# msp430_f249_ctk.net
KiCad netlist of a schematic drawn in EAGLE
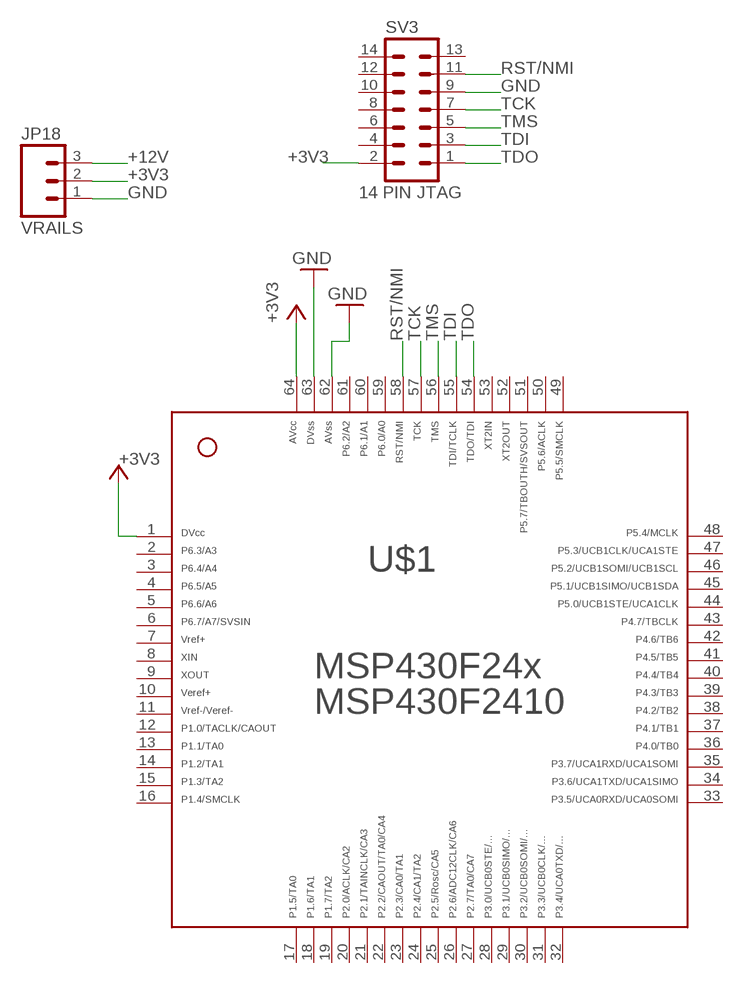
[diagram p0: schematic, sheet 1]

(export (version "E")
  (design (tool "Eeschema 10.0.6"))
  (components
    (comp (ref "JP18")
      (value "VRAILS")
      (footprint "eagle-import:SCREWTERMINAL-3.5MM-3")
      (libsource (lib "eagle-import") (part "M03SCREW"))
    )
    (comp (ref "SV3")
      (value "14 PIN JTAG")
      (footprint "eagle-import:ML14")
      (libsource (lib "eagle-import") (part "ML14"))
    )
    (comp (ref "U$1")
      (value "F24[X/10]---PM64")
      (footprint "eagle-import:PM_PAG64")
      (libsource (lib "eagle-import") (part "F24[X/10]---PM64"))
    )
  )
  (nets
    (net (code "1") (name "+3V3") (class "Default")
      (node (ref "JP18") (pin "2") (pinfunction "2_2") (pintype "passive"))
      (node (ref "SV3") (pin "2") (pinfunction "2_2") (pintype "passive"))
      (node (ref "U$1") (pin "1") (pinfunction "1_1") (pintype "power_in"))
      (node (ref "U$1") (pin "64") (pinfunction "64_64") (pintype "power_in"))
    )
    (net (code "2") (name "/+12V") (class "Default")
      (node (ref "JP18") (pin "3") (pinfunction "3_3") (pintype "passive"))
    )
    (net (code "3") (name "/RST{slash}NMI") (class "Default")
      (node (ref "SV3") (pin "11") (pinfunction "11_11") (pintype "passive"))
      (node (ref "U$1") (pin "58") (pinfunction "58_58") (pintype "input"))
    )
    (net (code "4") (name "/TCK") (class "Default")
      (node (ref "SV3") (pin "7") (pinfunction "7_7") (pintype "passive"))
      (node (ref "U$1") (pin "57") (pinfunction "57_57") (pintype "input"))
    )
    (net (code "5") (name "/TDI") (class "Default")
      (node (ref "SV3") (pin "3") (pinfunction "3_3") (pintype "passive"))
      (node (ref "U$1") (pin "55") (pinfunction "55_55") (pintype "input"))
    )
    (net (code "6") (name "/TDO") (class "Default")
      (node (ref "SV3") (pin "1") (pinfunction "1_1") (pintype "passive"))
      (node (ref "U$1") (pin "54") (pinfunction "54_54") (pintype "bidirectional"))
    )
    (net (code "7") (name "/TMS") (class "Default")
      (node (ref "SV3") (pin "5") (pinfunction "5_5") (pintype "passive"))
      (node (ref "U$1") (pin "56") (pinfunction "56_56") (pintype "input"))
    )
    (net (code "8") (name "GND") (class "Default")
      (node (ref "JP18") (pin "1") (pinfunction "1_1") (pintype "passive"))
      (node (ref "SV3") (pin "9") (pinfunction "9_9") (pintype "passive"))
      (node (ref "U$1") (pin "62") (pinfunction "62_62") (pintype "power_in"))
      (node (ref "U$1") (pin "63") (pinfunction "63_63") (pintype "power_in"))
    )
    (net (code "9") (name "unconnected-(SV3-Pad4)") (class "Default")
      (node (ref "SV3") (pin "4") (pinfunction "4_4") (pintype "passive"))
    )
    (net (code "10") (name "unconnected-(SV3-Pad6)") (class "Default")
      (node (ref "SV3") (pin "6") (pinfunction "6_6") (pintype "passive"))
    )
    (net (code "11") (name "unconnected-(SV3-Pad8)") (class "Default")
      (node (ref "SV3") (pin "8") (pinfunction "8_8") (pintype "passive"))
    )
    (net (code "12") (name "unconnected-(SV3-Pad10)") (class "Default")
      (node (ref "SV3") (pin "10") (pinfunction "10_10") (pintype "passive"))
    )
    (net (code "13") (name "unconnected-(SV3-Pad12)") (class "Default")
      (node (ref "SV3") (pin "12") (pinfunction "12_12") (pintype "passive"))
    )
    (net (code "14") (name "unconnected-(SV3-Pad13)") (class "Default")
      (node (ref "SV3") (pin "13") (pinfunction "13_13") (pintype "passive"))
    )
    (net (code "15") (name "unconnected-(SV3-Pad14)") (class "Default")
      (node (ref "SV3") (pin "14") (pinfunction "14_14") (pintype "passive"))
    )
    (net (code "16") (name "unconnected-(U$1-Pad2)") (class "Default")
      (node (ref "U$1") (pin "2") (pinfunction "2_2") (pintype "bidirectional"))
    )
    (net (code "17") (name "unconnected-(U$1-Pad3)") (class "Default")
      (node (ref "U$1") (pin "3") (pinfunction "3_3") (pintype "bidirectional"))
    )
    (net (code "18") (name "unconnected-(U$1-Pad4)") (class "Default")
      (node (ref "U$1") (pin "4") (pinfunction "4_4") (pintype "bidirectional"))
    )
    (net (code "19") (name "unconnected-(U$1-Pad5)") (class "Default")
      (node (ref "U$1") (pin "5") (pinfunction "5_5") (pintype "bidirectional"))
    )
    (net (code "20") (name "unconnected-(U$1-Pad6)") (class "Default")
      (node (ref "U$1") (pin "6") (pinfunction "6_6") (pintype "bidirectional"))
    )
    (net (code "21") (name "unconnected-(U$1-Pad7)") (class "Default")
      (node (ref "U$1") (pin "7") (pinfunction "7_7") (pintype "output"))
    )
    (net (code "22") (name "unconnected-(U$1-Pad8)") (class "Default")
      (node (ref "U$1") (pin "8") (pinfunction "8_8") (pintype "input"))
    )
    (net (code "23") (name "unconnected-(U$1-Pad9)") (class "Default")
      (node (ref "U$1") (pin "9") (pinfunction "9_9") (pintype "output"))
    )
    (net (code "24") (name "unconnected-(U$1-Pad10)") (class "Default")
      (node (ref "U$1") (pin "10") (pinfunction "10_10") (pintype "output"))
    )
    (net (code "25") (name "unconnected-(U$1-Pad11)") (class "Default")
      (node (ref "U$1") (pin "11") (pinfunction "11_11") (pintype "input"))
    )
    (net (code "26") (name "unconnected-(U$1-Pad12)") (class "Default")
      (node (ref "U$1") (pin "12") (pinfunction "12_12") (pintype "bidirectional"))
    )
    (net (code "27") (name "unconnected-(U$1-Pad13)") (class "Default")
      (node (ref "U$1") (pin "13") (pinfunction "13_13") (pintype "bidirectional"))
    )
    (net (code "28") (name "unconnected-(U$1-Pad14)") (class "Default")
      (node (ref "U$1") (pin "14") (pinfunction "14_14") (pintype "bidirectional"))
    )
    (net (code "29") (name "unconnected-(U$1-Pad15)") (class "Default")
      (node (ref "U$1") (pin "15") (pinfunction "15_15") (pintype "bidirectional"))
    )
    (net (code "30") (name "unconnected-(U$1-Pad16)") (class "Default")
      (node (ref "U$1") (pin "16") (pinfunction "16_16") (pintype "bidirectional"))
    )
    (net (code "31") (name "unconnected-(U$1-Pad17)") (class "Default")
      (node (ref "U$1") (pin "17") (pinfunction "17_17") (pintype "bidirectional"))
    )
    (net (code "32") (name "unconnected-(U$1-Pad18)") (class "Default")
      (node (ref "U$1") (pin "18") (pinfunction "18_18") (pintype "bidirectional"))
    )
    (net (code "33") (name "unconnected-(U$1-Pad19)") (class "Default")
      (node (ref "U$1") (pin "19") (pinfunction "19_19") (pintype "bidirectional"))
    )
    (net (code "34") (name "unconnected-(U$1-Pad20)") (class "Default")
      (node (ref "U$1") (pin "20") (pinfunction "20_20") (pintype "bidirectional"))
    )
    (net (code "35") (name "unconnected-(U$1-Pad21)") (class "Default")
      (node (ref "U$1") (pin "21") (pinfunction "21_21") (pintype "bidirectional"))
    )
    (net (code "36") (name "unconnected-(U$1-Pad22)") (class "Default")
      (node (ref "U$1") (pin "22") (pinfunction "22_22") (pintype "bidirectional"))
    )
    (net (code "37") (name "unconnected-(U$1-Pad23)") (class "Default")
      (node (ref "U$1") (pin "23") (pinfunction "23_23") (pintype "bidirectional"))
    )
    (net (code "38") (name "unconnected-(U$1-Pad24)") (class "Default")
      (node (ref "U$1") (pin "24") (pinfunction "24_24") (pintype "bidirectional"))
    )
    (net (code "39") (name "unconnected-(U$1-Pad25)") (class "Default")
      (node (ref "U$1") (pin "25") (pinfunction "25_25") (pintype "bidirectional"))
    )
    (net (code "40") (name "unconnected-(U$1-Pad26)") (class "Default")
      (node (ref "U$1") (pin "26") (pinfunction "26_26") (pintype "bidirectional"))
    )
    (net (code "41") (name "unconnected-(U$1-Pad27)") (class "Default")
      (node (ref "U$1") (pin "27") (pinfunction "27_27") (pintype "bidirectional"))
    )
    (net (code "42") (name "unconnected-(U$1-Pad28)") (class "Default")
      (node (ref "U$1") (pin "28") (pinfunction "28_28") (pintype "bidirectional"))
    )
    (net (code "43") (name "unconnected-(U$1-Pad29)") (class "Default")
      (node (ref "U$1") (pin "29") (pinfunction "29_29") (pintype "bidirectional"))
    )
    (net (code "44") (name "unconnected-(U$1-Pad30)") (class "Default")
      (node (ref "U$1") (pin "30") (pinfunction "30_30") (pintype "bidirectional"))
    )
    (net (code "45") (name "unconnected-(U$1-Pad31)") (class "Default")
      (node (ref "U$1") (pin "31") (pinfunction "31_31") (pintype "bidirectional"))
    )
    (net (code "46") (name "unconnected-(U$1-Pad32)") (class "Default")
      (node (ref "U$1") (pin "32") (pinfunction "32_32") (pintype "bidirectional"))
    )
    (net (code "47") (name "unconnected-(U$1-Pad33)") (class "Default")
      (node (ref "U$1") (pin "33") (pinfunction "33_33") (pintype "bidirectional"))
    )
    (net (code "48") (name "unconnected-(U$1-Pad34)") (class "Default")
      (node (ref "U$1") (pin "34") (pinfunction "34_34") (pintype "bidirectional"))
    )
    (net (code "49") (name "unconnected-(U$1-Pad35)") (class "Default")
      (node (ref "U$1") (pin "35") (pinfunction "35_35") (pintype "bidirectional"))
    )
    (net (code "50") (name "unconnected-(U$1-Pad36)") (class "Default")
      (node (ref "U$1") (pin "36") (pinfunction "36_36") (pintype "bidirectional"))
    )
    (net (code "51") (name "unconnected-(U$1-Pad37)") (class "Default")
      (node (ref "U$1") (pin "37") (pinfunction "37_37") (pintype "bidirectional"))
    )
    (net (code "52") (name "unconnected-(U$1-Pad38)") (class "Default")
      (node (ref "U$1") (pin "38") (pinfunction "38_38") (pintype "bidirectional"))
    )
    (net (code "53") (name "unconnected-(U$1-Pad39)") (class "Default")
      (node (ref "U$1") (pin "39") (pinfunction "39_39") (pintype "bidirectional"))
    )
    (net (code "54") (name "unconnected-(U$1-Pad40)") (class "Default")
      (node (ref "U$1") (pin "40") (pinfunction "40_40") (pintype "bidirectional"))
    )
    (net (code "55") (name "unconnected-(U$1-Pad41)") (class "Default")
      (node (ref "U$1") (pin "41") (pinfunction "41_41") (pintype "bidirectional"))
    )
    (net (code "56") (name "unconnected-(U$1-Pad42)") (class "Default")
      (node (ref "U$1") (pin "42") (pinfunction "42_42") (pintype "bidirectional"))
    )
    (net (code "57") (name "unconnected-(U$1-Pad43)") (class "Default")
      (node (ref "U$1") (pin "43") (pinfunction "43_43") (pintype "bidirectional"))
    )
    (net (code "58") (name "unconnected-(U$1-Pad44)") (class "Default")
      (node (ref "U$1") (pin "44") (pinfunction "44_44") (pintype "bidirectional"))
    )
    (net (code "59") (name "unconnected-(U$1-Pad45)") (class "Default")
      (node (ref "U$1") (pin "45") (pinfunction "45_45") (pintype "bidirectional"))
    )
    (net (code "60") (name "unconnected-(U$1-Pad46)") (class "Default")
      (node (ref "U$1") (pin "46") (pinfunction "46_46") (pintype "bidirectional"))
    )
    (net (code "61") (name "unconnected-(U$1-Pad47)") (class "Default")
      (node (ref "U$1") (pin "47") (pinfunction "47_47") (pintype "bidirectional"))
    )
    (net (code "62") (name "unconnected-(U$1-Pad48)") (class "Default")
      (node (ref "U$1") (pin "48") (pinfunction "48_48") (pintype "bidirectional"))
    )
    (net (code "63") (name "unconnected-(U$1-Pad49)") (class "Default")
      (node (ref "U$1") (pin "49") (pinfunction "49_49") (pintype "bidirectional"))
    )
    (net (code "64") (name "unconnected-(U$1-Pad50)") (class "Default")
      (node (ref "U$1") (pin "50") (pinfunction "50_50") (pintype "bidirectional"))
    )
    (net (code "65") (name "unconnected-(U$1-Pad51)") (class "Default")
      (node (ref "U$1") (pin "51") (pinfunction "51_51") (pintype "bidirectional"))
    )
    (net (code "66") (name "unconnected-(U$1-Pad52)") (class "Default")
      (node (ref "U$1") (pin "52") (pinfunction "52_52") (pintype "output"))
    )
    (net (code "67") (name "unconnected-(U$1-Pad53)") (class "Default")
      (node (ref "U$1") (pin "53") (pinfunction "53_53") (pintype "input"))
    )
    (net (code "68") (name "unconnected-(U$1-Pad59)") (class "Default")
      (node (ref "U$1") (pin "59") (pinfunction "59_59") (pintype "bidirectional"))
    )
    (net (code "69") (name "unconnected-(U$1-Pad60)") (class "Default")
      (node (ref "U$1") (pin "60") (pinfunction "60_60") (pintype "bidirectional"))
    )
    (net (code "70") (name "unconnected-(U$1-Pad61)") (class "Default")
      (node (ref "U$1") (pin "61") (pinfunction "61_61") (pintype "bidirectional"))
    )
  )
)
